# CH32L103F8P6-R0.net
KiCad netlist of a schematic drawn in Altium Designer
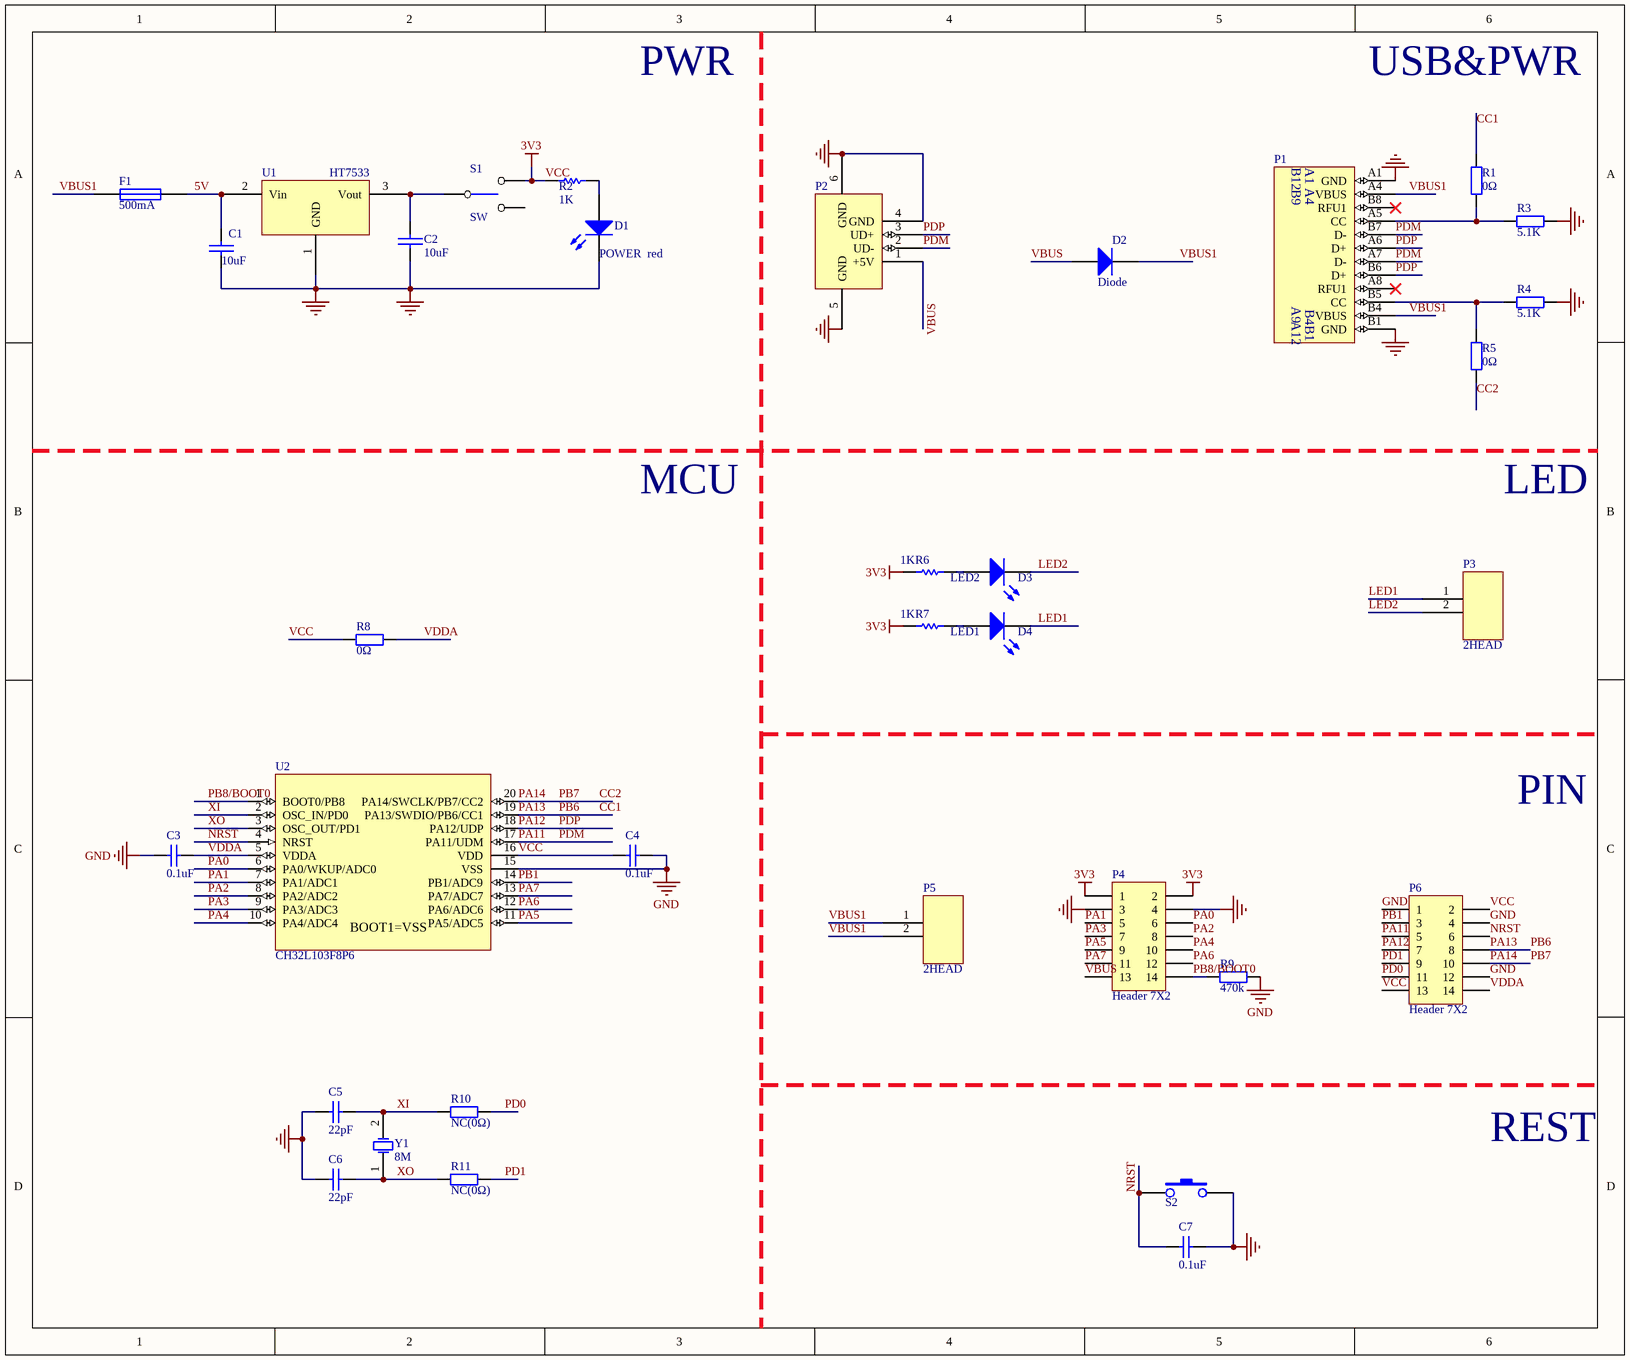
[diagram p0: CH32L103F8P6-R0.SchDoc]

(export (version "E")
  (design (tool "Eeschema 10.0.6"))
  (components
    (comp (ref "C1")
      (value "10uF")
      (footprint "0603_C")
      (description "Capacitor")
      (libsource (lib "*") (part "CAP"))
    )
    (comp (ref "C2")
      (value "10uF")
      (footprint "0603_C")
      (description "Capacitor")
      (libsource (lib "*") (part "CAP"))
    )
    (comp (ref "C3")
      (value "0.1uF")
      (footprint "0603_C")
      (description "Capacitor")
      (fields (field (name "PUBLISHER") "Altium Limited"))
      (libsource (lib "*") (part "Cap"))
    )
    (comp (ref "C4")
      (value "0.1uF")
      (footprint "0603_C")
      (description "Capacitor")
      (fields (field (name "PUBLISHER") "Altium Limited"))
      (libsource (lib "*") (part "Cap"))
    )
    (comp (ref "C5")
      (value "22pF")
      (footprint "0603_C")
      (description "Capacitor")
      (fields (field (name "PUBLISHER") "Altium Limited"))
      (libsource (lib "*") (part "Cap"))
    )
    (comp (ref "C6")
      (value "22pF")
      (footprint "0603_C")
      (description "Capacitor")
      (fields (field (name "PUBLISHER") "Altium Limited"))
      (libsource (lib "*") (part "Cap"))
    )
    (comp (ref "C7")
      (value "0.1uF")
      (footprint "0603_C")
      (description "Capacitor")
      (fields (field (name "PUBLISHER") "Altium Limited"))
      (libsource (lib "*") (part "Cap"))
    )
    (comp (ref "D1")
      (value "POWER  red")
      (footprint "0603+")
      (description "Typical INFRARED GaAs LED")
      (fields (field (name "PUBLISHER") "Altium Limited"))
      (libsource (lib "*") (part "LED0"))
    )
    (comp (ref "D2")
      (value "Diode")
      (footprint "SOD-123")
      (description "Default Diode")
      (fields (field (name "PUBLISHER") "Altium Limited"))
      (libsource (lib "Miscellaneous Devices") (part "Diode"))
    )
    (comp (ref "D3")
      (value "LED2")
      (footprint "0603+")
      (description "Typical INFRARED GaAs LED")
      (fields (field (name "PUBLISHER") "Altium Limited"))
      (libsource (lib "*") (part "LED0"))
    )
    (comp (ref "D4")
      (value "LED1")
      (footprint "0603+")
      (description "Typical INFRARED GaAs LED")
      (fields (field (name "PUBLISHER") "Altium Limited"))
      (libsource (lib "*") (part "LED0"))
    )
    (comp (ref "F1")
      (value "500mA")
      (footprint "0603")
      (description "Fuse")
      (libsource (lib "*") (part "FUSE1"))
    )
    (comp (ref "P1")
      (value "TYPE-C")
      (footprint "TYPE-C-Receptacle-2.0")
      (libsource (lib "*") (part "TYPE-C1"))
    )
    (comp (ref "P2")
      (value "USB_A")
      (footprint "USBAF")
      (description "USB Port")
      (libsource (lib "*") (part "USB"))
    )
    (comp (ref "P3") (value "2HEAD") (footprint "SIP2-2.54mm") (libsource (lib "*") (part "2HEAD")))
    (comp (ref "P4")
      (value "Header 7X2")
      (footprint "IDC14-2.54mm")
      (description "Header, 7-Pin, Dual row")
      (fields (field (name "PUBLISHER") "Altium Limited"))
      (libsource (lib "Miscellaneous Connectors") (part "Header 7X2"))
    )
    (comp (ref "P5") (value "2HEAD") (footprint "SIP2-2.54mm") (libsource (lib "*") (part "2HEAD")))
    (comp (ref "P6")
      (value "Header 7X2")
      (footprint "IDC14-2.54mm")
      (description "Header, 7-Pin, Dual row")
      (fields (field (name "PUBLISHER") "Altium Limited"))
      (libsource (lib "Miscellaneous Connectors") (part "Header 7X2"))
    )
    (comp (ref "R1")
      (value "0Ω")
      (footprint "0603")
      (description "Resistor")
      (libsource (lib "") (part "Res2_2"))
    )
    (comp (ref "R2")
      (value "1K")
      (footprint "0603")
      (description "Semiconductor Resistor")
      (libsource (lib "*") (part "Res Semi"))
    )
    (comp (ref "R3")
      (value "5.1K")
      (footprint "0603")
      (description "Resistor")
      (libsource (lib "Miscellaneous Devices") (part "Res2"))
    )
    (comp (ref "R4")
      (value "5.1K")
      (footprint "0603")
      (description "Resistor")
      (libsource (lib "Miscellaneous Devices") (part "Res2"))
    )
    (comp (ref "R5")
      (value "0Ω")
      (footprint "0603")
      (description "Resistor")
      (libsource (lib "") (part "Res2_2"))
    )
    (comp (ref "R6")
      (value "1K")
      (footprint "0603")
      (description "Semiconductor Resistor")
      (libsource (lib "*") (part "Res Semi"))
    )
    (comp (ref "R7")
      (value "1K")
      (footprint "0603")
      (description "Semiconductor Resistor")
      (libsource (lib "*") (part "Res Semi"))
    )
    (comp (ref "R8")
      (value "0Ω")
      (footprint "0603")
      (description "Resistor")
      (libsource (lib "Miscellaneous Devices") (part "Res2"))
    )
    (comp (ref "R9")
      (value "470k")
      (footprint "0603")
      (description "Resistor")
      (libsource (lib "Miscellaneous Devices") (part "Res2"))
    )
    (comp (ref "R10")
      (value "NC(0Ω)")
      (footprint "0603")
      (description "Resistor")
      (libsource (lib "") (part "Res2_1"))
    )
    (comp (ref "R11")
      (value "NC(0Ω)")
      (footprint "0603")
      (description "Resistor")
      (libsource (lib "") (part "Res2_1"))
    )
    (comp (ref "S1") (value "SW") (footprint "SW1") (libsource (lib "*") (part "SW")))
    (comp (ref "S2") (value "KEY") (footprint "贴片按键") (libsource (lib "*") (part "KEY")))
    (comp (ref "U1")
      (value "HT7533")
      (footprint "SOT-89")
      (libsource (lib "wch_sch_others") (part "1117-3.3V"))
    )
    (comp (ref "U2")
      (value "CH32L103F8P6")
      (footprint "TSSOP20")
      (description "RISC-V LMD-MCU, 96MHz, USB, Type-C/PD, CAN, OPA, lower power")
      (libsource (lib "DHXXXSCH") (part "CH32L103F8P6"))
    )
    (comp (ref "Y1")
      (value "8M")
      (footprint "XT_AT49")
      (description "Crystal Oscillator")
      (fields (field (name "PUBLISHER") "Altium Limited"))
      (libsource (lib "*") (part "XTAL"))
    )
  )
  (nets
    (net (code "1") (name "/5V") (class "Default")
      (node (ref "C1") (pin "1") (pinfunction "1_1") (pintype "passive"))
      (node (ref "F1") (pin "2") (pinfunction "2_2") (pintype "passive"))
      (node (ref "U1") (pin "2") (pinfunction "Vin_2") (pintype "passive"))
    )
    (net (code "3") (name "/CC1") (class "Default")
      (node (ref "P6") (pin "8") (pinfunction "8_8") (pintype "passive"))
      (node (ref "R1") (pin "2") (pinfunction "2_2") (pintype "passive"))
      (node (ref "U2") (pin "19") (pinfunction "PA13/SWDIO/PB6/CC1_19") (pintype "bidirectional"))
    )
    (net (code "4") (name "/CC2") (class "Default")
      (node (ref "P6") (pin "10") (pinfunction "10_10") (pintype "passive"))
      (node (ref "R5") (pin "1") (pinfunction "1_1") (pintype "passive"))
      (node (ref "U2") (pin "20") (pinfunction "PA14/SWCLK/PB7/CC2_20") (pintype "bidirectional"))
    )
    (net (code "5") (name "/LED1") (class "Default")
      (node (ref "D4") (pin "2") (pinfunction "K_2") (pintype "passive"))
      (node (ref "P3") (pin "1") (pintype "passive"))
    )
    (net (code "6") (name "/LED2") (class "Default")
      (node (ref "D3") (pin "2") (pinfunction "K_2") (pintype "passive"))
      (node (ref "P3") (pin "2") (pintype "passive"))
    )
    (net (code "7") (name "/NRST") (class "Default")
      (node (ref "C7") (pin "2") (pinfunction "2_2") (pintype "passive"))
      (node (ref "P6") (pin "6") (pinfunction "6_6") (pintype "passive"))
      (node (ref "S2") (pin "1") (pinfunction "1_1") (pintype "passive"))
      (node (ref "U2") (pin "4") (pinfunction "NRST_4") (pintype "input"))
    )
    (net (code "8") (name "/PA0") (class "Default")
      (node (ref "P4") (pin "6") (pinfunction "6_6") (pintype "passive"))
      (node (ref "U2") (pin "6") (pinfunction "PA0/WKUP/ADC0_6") (pintype "bidirectional"))
    )
    (net (code "9") (name "/PA1") (class "Default")
      (node (ref "P4") (pin "5") (pinfunction "5_5") (pintype "passive"))
      (node (ref "U2") (pin "7") (pinfunction "PA1/ADC1_7") (pintype "bidirectional"))
    )
    (net (code "10") (name "/PA2") (class "Default")
      (node (ref "P4") (pin "8") (pinfunction "8_8") (pintype "passive"))
      (node (ref "U2") (pin "8") (pinfunction "PA2/ADC2_8") (pintype "bidirectional"))
    )
    (net (code "11") (name "/PA3") (class "Default")
      (node (ref "P4") (pin "7") (pinfunction "7_7") (pintype "passive"))
      (node (ref "U2") (pin "9") (pinfunction "PA3/ADC3_9") (pintype "bidirectional"))
    )
    (net (code "12") (name "/PA4") (class "Default")
      (node (ref "P4") (pin "10") (pinfunction "10_10") (pintype "passive"))
      (node (ref "U2") (pin "10") (pinfunction "PA4/ADC4_10") (pintype "bidirectional"))
    )
    (net (code "13") (name "/PA5") (class "Default")
      (node (ref "P4") (pin "9") (pinfunction "9_9") (pintype "passive"))
      (node (ref "U2") (pin "11") (pinfunction "PA5/ADC5_11") (pintype "bidirectional"))
    )
    (net (code "14") (name "/PA6") (class "Default")
      (node (ref "P4") (pin "12") (pinfunction "12_12") (pintype "passive"))
      (node (ref "U2") (pin "12") (pinfunction "PA6/ADC6_12") (pintype "bidirectional"))
    )
    (net (code "15") (name "/PA7") (class "Default")
      (node (ref "P4") (pin "11") (pinfunction "11_11") (pintype "passive"))
      (node (ref "U2") (pin "13") (pinfunction "PA7/ADC7_13") (pintype "bidirectional"))
    )
    (net (code "16") (name "/PA11") (class "Default")
      (node (ref "P1") (pin "A7") (pinfunction "D-_A7") (pintype "bidirectional"))
      (node (ref "P1") (pin "B7") (pinfunction "D-_B7") (pintype "bidirectional"))
      (node (ref "P2") (pin "2") (pinfunction "UD-_2") (pintype "bidirectional"))
      (node (ref "P6") (pin "5") (pinfunction "5_5") (pintype "passive"))
      (node (ref "U2") (pin "17") (pinfunction "PA11/UDM_17") (pintype "bidirectional"))
    )
    (net (code "17") (name "/PA12") (class "Default")
      (node (ref "P1") (pin "A6") (pinfunction "D+_A6") (pintype "bidirectional"))
      (node (ref "P1") (pin "B6") (pinfunction "D+_B6") (pintype "bidirectional"))
      (node (ref "P2") (pin "3") (pinfunction "UD+_3") (pintype "bidirectional"))
      (node (ref "P6") (pin "7") (pinfunction "7_7") (pintype "passive"))
      (node (ref "U2") (pin "18") (pinfunction "PA12/UDP_18") (pintype "bidirectional"))
    )
    (net (code "18") (name "/PB1") (class "Default")
      (node (ref "P6") (pin "3") (pinfunction "3_3") (pintype "passive"))
      (node (ref "U2") (pin "14") (pinfunction "PB1/ADC9_14") (pintype "bidirectional"))
    )
    (net (code "19") (name "/PB8{slash}BOOT0") (class "Default")
      (node (ref "P4") (pin "14") (pinfunction "14_14") (pintype "passive"))
      (node (ref "R9") (pin "1") (pinfunction "1_1") (pintype "passive"))
      (node (ref "U2") (pin "1") (pinfunction "BOOT0/PB8_1") (pintype "bidirectional"))
    )
    (net (code "20") (name "/PD0") (class "Default")
      (node (ref "P6") (pin "11") (pinfunction "11_11") (pintype "passive"))
      (node (ref "R10") (pin "1") (pinfunction "1_1") (pintype "passive"))
    )
    (net (code "21") (name "/PD1") (class "Default")
      (node (ref "P6") (pin "9") (pinfunction "9_9") (pintype "passive"))
      (node (ref "R11") (pin "1") (pinfunction "1_1") (pintype "passive"))
    )
    (net (code "22") (name "/VBUS") (class "Default")
      (node (ref "D2") (pin "1") (pinfunction "A_1") (pintype "passive"))
      (node (ref "P2") (pin "1") (pinfunction "+5V_1") (pintype "power_in"))
      (node (ref "P4") (pin "13") (pinfunction "13_13") (pintype "passive"))
    )
    (net (code "23") (name "/VBUS1") (class "Default")
      (node (ref "D2") (pin "2") (pinfunction "K_2") (pintype "passive"))
      (node (ref "F1") (pin "1") (pinfunction "1_1") (pintype "passive"))
      (node (ref "P1") (pin "A4") (pinfunction "VBUS_A4") (pintype "bidirectional"))
      (node (ref "P1") (pin "B4") (pinfunction "VBUS_B4") (pintype "bidirectional"))
      (node (ref "P5") (pin "1") (pintype "passive"))
      (node (ref "P5") (pin "2") (pintype "passive"))
    )
    (net (code "24") (name "/VDDA") (class "Default")
      (node (ref "C3") (pin "1") (pinfunction "1_1") (pintype "passive"))
      (node (ref "P6") (pin "14") (pinfunction "14_14") (pintype "passive"))
      (node (ref "R8") (pin "2") (pinfunction "2_2") (pintype "passive"))
      (node (ref "U2") (pin "5") (pinfunction "VDDA_5") (pintype "bidirectional"))
    )
    (net (code "25") (name "/XI") (class "Default")
      (node (ref "C5") (pin "2") (pinfunction "2_2") (pintype "passive"))
      (node (ref "R10") (pin "2") (pinfunction "2_2") (pintype "passive"))
      (node (ref "U2") (pin "2") (pinfunction "OSC_IN/PD0_2") (pintype "bidirectional"))
      (node (ref "Y1") (pin "2") (pinfunction "OSC2_2") (pintype "passive"))
    )
    (net (code "26") (name "/XO") (class "Default")
      (node (ref "C6") (pin "2") (pinfunction "2_2") (pintype "passive"))
      (node (ref "R11") (pin "2") (pinfunction "2_2") (pintype "passive"))
      (node (ref "U2") (pin "3") (pinfunction "OSC_OUT/PD1_3") (pintype "bidirectional"))
      (node (ref "Y1") (pin "1") (pinfunction "OSC1_1") (pintype "passive"))
    )
    (net (code "27") (name "3V3") (class "Default")
      (node (ref "C4") (pin "1") (pinfunction "1_1") (pintype "passive"))
      (node (ref "P4") (pin "1") (pinfunction "1_1") (pintype "passive"))
      (node (ref "P4") (pin "2") (pinfunction "2_2") (pintype "passive"))
      (node (ref "P6") (pin "13") (pinfunction "13_13") (pintype "passive"))
      (node (ref "P6") (pin "2") (pinfunction "2_2") (pintype "passive"))
      (node (ref "R2") (pin "2") (pinfunction "2_2") (pintype "passive"))
      (node (ref "R6") (pin "1") (pinfunction "1_1") (pintype "passive"))
      (node (ref "R7") (pin "1") (pinfunction "1_1") (pintype "passive"))
      (node (ref "R8") (pin "1") (pinfunction "1_1") (pintype "passive"))
      (node (ref "S1") (pin "3") (pinfunction "3_3") (pintype "passive"))
      (node (ref "U2") (pin "16") (pinfunction "VDD_16") (pintype "power_in"))
    )
    (net (code "28") (name "GND") (class "Default")
      (node (ref "C1") (pin "2") (pinfunction "2_2") (pintype "passive"))
      (node (ref "C2") (pin "2") (pinfunction "2_2") (pintype "passive"))
      (node (ref "C3") (pin "2") (pinfunction "2_2") (pintype "passive"))
      (node (ref "C4") (pin "2") (pinfunction "2_2") (pintype "passive"))
      (node (ref "C5") (pin "1") (pinfunction "1_1") (pintype "passive"))
      (node (ref "C6") (pin "1") (pinfunction "1_1") (pintype "passive"))
      (node (ref "C7") (pin "1") (pinfunction "1_1") (pintype "passive"))
      (node (ref "D1") (pin "2") (pinfunction "K_2") (pintype "passive"))
      (node (ref "P1") (pin "A1") (pinfunction "GND_A1") (pintype "bidirectional"))
      (node (ref "P1") (pin "B1") (pinfunction "GND_B1") (pintype "bidirectional"))
      (node (ref "P2") (pin "4") (pinfunction "GND_4") (pintype "power_in"))
      (node (ref "P2") (pin "5") (pinfunction "GND_5") (pintype "power_in"))
      (node (ref "P2") (pin "6") (pinfunction "GND_6") (pintype "power_in"))
      (node (ref "P4") (pin "3") (pinfunction "3_3") (pintype "passive"))
      (node (ref "P4") (pin "4") (pinfunction "4_4") (pintype "passive"))
      (node (ref "P6") (pin "1") (pinfunction "1_1") (pintype "passive"))
      (node (ref "P6") (pin "12") (pinfunction "12_12") (pintype "passive"))
      (node (ref "P6") (pin "4") (pinfunction "4_4") (pintype "passive"))
      (node (ref "R3") (pin "2") (pinfunction "2_2") (pintype "passive"))
      (node (ref "R4") (pin "2") (pinfunction "2_2") (pintype "passive"))
      (node (ref "R9") (pin "2") (pinfunction "2_2") (pintype "passive"))
      (node (ref "S2") (pin "3") (pinfunction "3_3") (pintype "passive"))
      (node (ref "U1") (pin "1") (pinfunction "GND_1") (pintype "passive"))
      (node (ref "U2") (pin "15") (pinfunction "VSS_15") (pintype "power_in"))
    )
    (net (code "29") (name "Net-(D1-A)") (class "Default")
      (node (ref "D1") (pin "1") (pinfunction "A_1") (pintype "passive"))
      (node (ref "R2") (pin "1") (pinfunction "1_1") (pintype "passive"))
    )
    (net (code "30") (name "Net-(D3-A)") (class "Default")
      (node (ref "D3") (pin "1") (pinfunction "A_1") (pintype "passive"))
      (node (ref "R6") (pin "2") (pinfunction "2_2") (pintype "passive"))
    )
    (net (code "31") (name "Net-(D4-A)") (class "Default")
      (node (ref "D4") (pin "1") (pinfunction "A_1") (pintype "passive"))
      (node (ref "R7") (pin "2") (pinfunction "2_2") (pintype "passive"))
    )
    (net (code "32") (name "Net-(P1-CC-PadA5)") (class "Default")
      (node (ref "P1") (pin "A5") (pinfunction "CC_A5") (pintype "bidirectional"))
      (node (ref "R1") (pin "1") (pinfunction "1_1") (pintype "passive"))
      (node (ref "R3") (pin "1") (pinfunction "1_1") (pintype "passive"))
    )
    (net (code "33") (name "Net-(P1-CC-PadB5)") (class "Default")
      (node (ref "P1") (pin "B5") (pinfunction "CC_B5") (pintype "bidirectional"))
      (node (ref "R4") (pin "1") (pinfunction "1_1") (pintype "passive"))
      (node (ref "R5") (pin "2") (pinfunction "2_2") (pintype "passive"))
    )
    (net (code "34") (name "Net-(U1-Vout)") (class "Default")
      (node (ref "C2") (pin "1") (pinfunction "1_1") (pintype "passive"))
      (node (ref "S1") (pin "1") (pinfunction "1_1") (pintype "passive"))
      (node (ref "U1") (pin "3") (pinfunction "Vout_3") (pintype "passive"))
    )
    (net (code "35") (name "unconnected-(P1-RFU1-PadA8)") (class "Default")
      (node (ref "P1") (pin "A8") (pinfunction "RFU1_A8") (pintype "bidirectional+no_connect"))
    )
    (net (code "36") (name "unconnected-(P1-RFU1-PadB8)") (class "Default")
      (node (ref "P1") (pin "B8") (pinfunction "RFU1_B8") (pintype "bidirectional+no_connect"))
    )
    (net (code "37") (name "unconnected-(S1-Pad2)") (class "Default")
      (node (ref "S1") (pin "2") (pinfunction "2_2") (pintype "passive"))
    )
  )
)
